# 40_Temp.net
KiCad netlist of a schematic drawn in Altium Designer
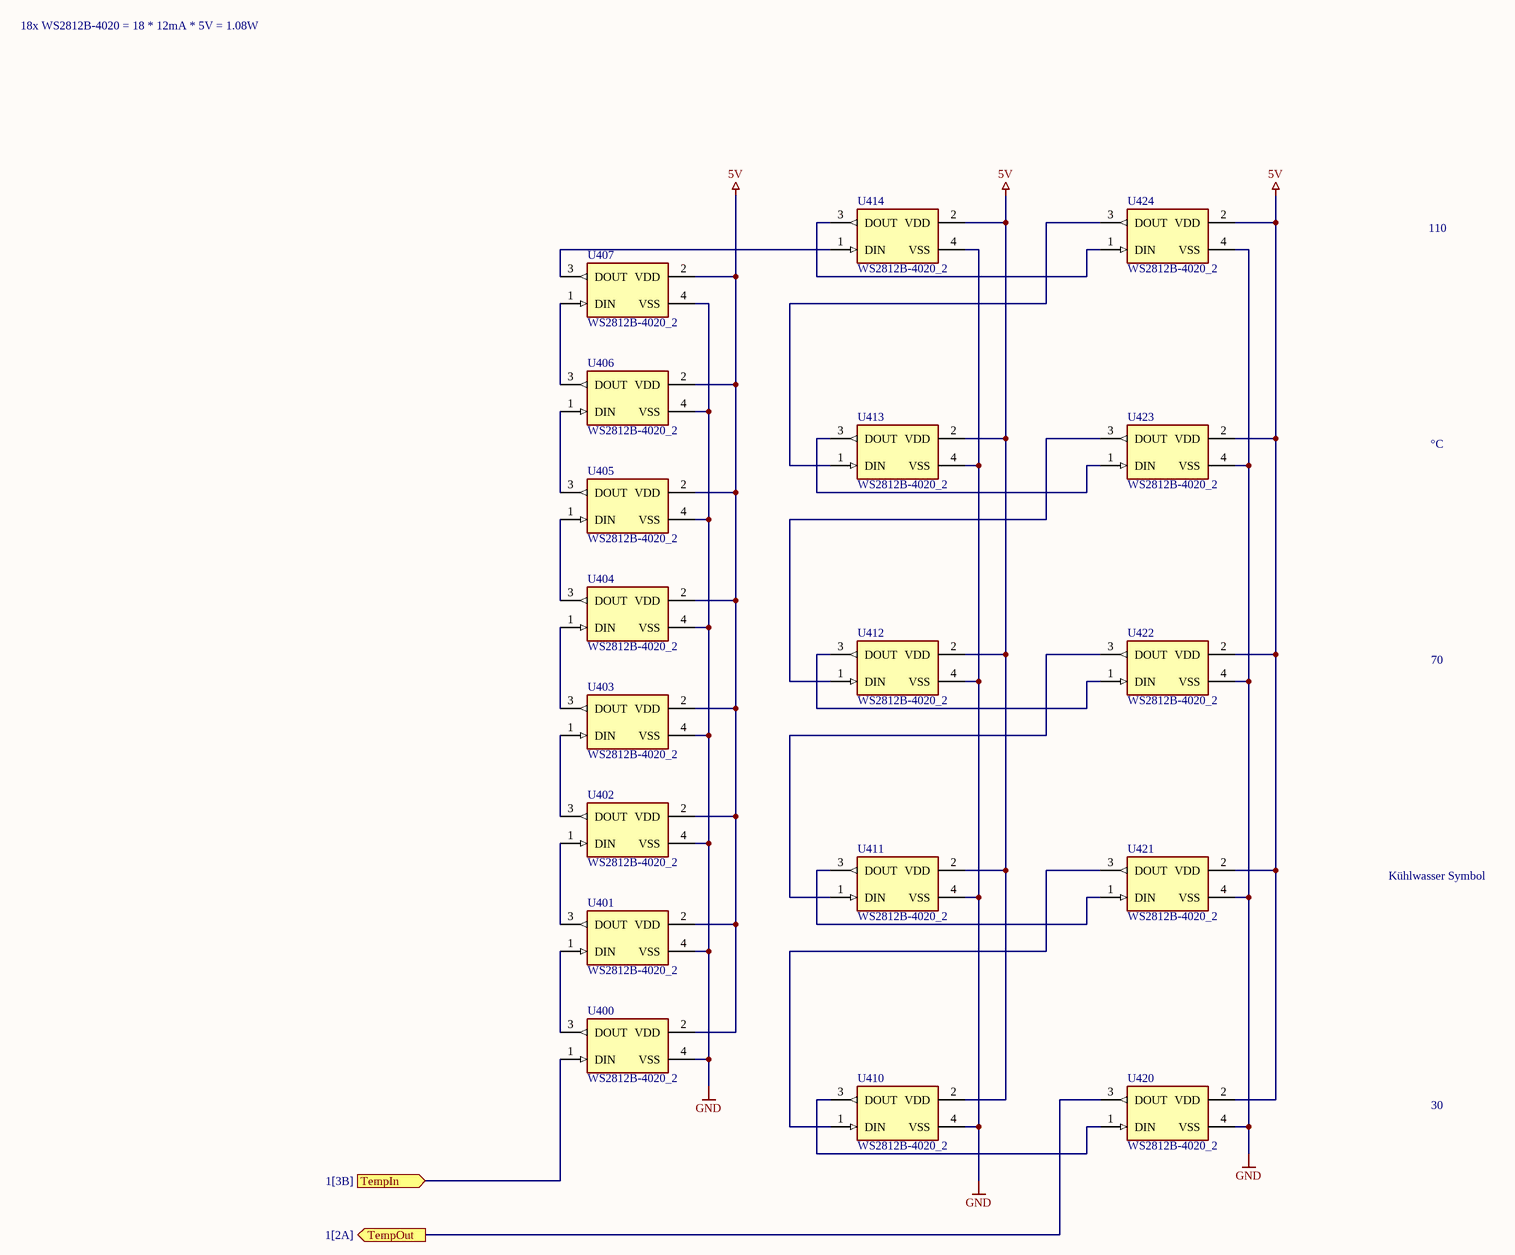
[diagram p0: 40_Temp.SchDoc]

(export (version "E")
  (design (tool "Eeschema 10.0.6"))
  (components
    (comp (ref "U400")
      (value "WS2812B-4020_2")
      (footprint "LED_WS2812B-4020")
      (description "12mA RGB SMD,2x4mm Light Emitting Diodes")
      (fields (field (name "MP") "WS2812B-4020") (field (name "MF") "Worldsemi"))
      (libsource (lib "AltiumLib_MILUTIN") (part "WS2812B-4020_2"))
    )
    (comp (ref "U401")
      (value "WS2812B-4020_2")
      (footprint "LED_WS2812B-4020")
      (description "12mA RGB SMD,2x4mm Light Emitting Diodes")
      (fields (field (name "MP") "WS2812B-4020") (field (name "MF") "Worldsemi"))
      (libsource (lib "AltiumLib_MILUTIN") (part "WS2812B-4020_2"))
    )
    (comp (ref "U402")
      (value "WS2812B-4020_2")
      (footprint "LED_WS2812B-4020")
      (description "12mA RGB SMD,2x4mm Light Emitting Diodes")
      (fields (field (name "MP") "WS2812B-4020") (field (name "MF") "Worldsemi"))
      (libsource (lib "AltiumLib_MILUTIN") (part "WS2812B-4020_2"))
    )
    (comp (ref "U403")
      (value "WS2812B-4020_2")
      (footprint "LED_WS2812B-4020")
      (description "12mA RGB SMD,2x4mm Light Emitting Diodes")
      (fields (field (name "MP") "WS2812B-4020") (field (name "MF") "Worldsemi"))
      (libsource (lib "AltiumLib_MILUTIN") (part "WS2812B-4020_2"))
    )
    (comp (ref "U404")
      (value "WS2812B-4020_2")
      (footprint "LED_WS2812B-4020")
      (description "12mA RGB SMD,2x4mm Light Emitting Diodes")
      (fields (field (name "MP") "WS2812B-4020") (field (name "MF") "Worldsemi"))
      (libsource (lib "AltiumLib_MILUTIN") (part "WS2812B-4020_2"))
    )
    (comp (ref "U405")
      (value "WS2812B-4020_2")
      (footprint "LED_WS2812B-4020")
      (description "12mA RGB SMD,2x4mm Light Emitting Diodes")
      (fields (field (name "MP") "WS2812B-4020") (field (name "MF") "Worldsemi"))
      (libsource (lib "AltiumLib_MILUTIN") (part "WS2812B-4020_2"))
    )
    (comp (ref "U406")
      (value "WS2812B-4020_2")
      (footprint "LED_WS2812B-4020")
      (description "12mA RGB SMD,2x4mm Light Emitting Diodes")
      (fields (field (name "MP") "WS2812B-4020") (field (name "MF") "Worldsemi"))
      (libsource (lib "AltiumLib_MILUTIN") (part "WS2812B-4020_2"))
    )
    (comp (ref "U407")
      (value "WS2812B-4020_2")
      (footprint "LED_WS2812B-4020")
      (description "12mA RGB SMD,2x4mm Light Emitting Diodes")
      (fields (field (name "MP") "WS2812B-4020") (field (name "MF") "Worldsemi"))
      (libsource (lib "AltiumLib_MILUTIN") (part "WS2812B-4020_2"))
    )
    (comp (ref "U410")
      (value "WS2812B-4020_2")
      (footprint "LED_WS2812B-4020")
      (description "12mA RGB SMD,2x4mm Light Emitting Diodes")
      (fields (field (name "MP") "WS2812B-4020") (field (name "MF") "Worldsemi"))
      (libsource (lib "AltiumLib_MILUTIN") (part "WS2812B-4020_2"))
    )
    (comp (ref "U411")
      (value "WS2812B-4020_2")
      (footprint "LED_WS2812B-4020")
      (description "12mA RGB SMD,2x4mm Light Emitting Diodes")
      (fields (field (name "MP") "WS2812B-4020") (field (name "MF") "Worldsemi"))
      (libsource (lib "AltiumLib_MILUTIN") (part "WS2812B-4020_2"))
    )
    (comp (ref "U412")
      (value "WS2812B-4020_2")
      (footprint "LED_WS2812B-4020")
      (description "12mA RGB SMD,2x4mm Light Emitting Diodes")
      (fields (field (name "MP") "WS2812B-4020") (field (name "MF") "Worldsemi"))
      (libsource (lib "AltiumLib_MILUTIN") (part "WS2812B-4020_2"))
    )
    (comp (ref "U413")
      (value "WS2812B-4020_2")
      (footprint "LED_WS2812B-4020")
      (description "12mA RGB SMD,2x4mm Light Emitting Diodes")
      (fields (field (name "MP") "WS2812B-4020") (field (name "MF") "Worldsemi"))
      (libsource (lib "AltiumLib_MILUTIN") (part "WS2812B-4020_2"))
    )
    (comp (ref "U414")
      (value "WS2812B-4020_2")
      (footprint "LED_WS2812B-4020")
      (description "12mA RGB SMD,2x4mm Light Emitting Diodes")
      (fields (field (name "MP") "WS2812B-4020") (field (name "MF") "Worldsemi"))
      (libsource (lib "AltiumLib_MILUTIN") (part "WS2812B-4020_2"))
    )
    (comp (ref "U420")
      (value "WS2812B-4020_2")
      (footprint "LED_WS2812B-4020")
      (description "12mA RGB SMD,2x4mm Light Emitting Diodes")
      (fields (field (name "MP") "WS2812B-4020") (field (name "MF") "Worldsemi"))
      (libsource (lib "AltiumLib_MILUTIN") (part "WS2812B-4020_2"))
    )
    (comp (ref "U421")
      (value "WS2812B-4020_2")
      (footprint "LED_WS2812B-4020")
      (description "12mA RGB SMD,2x4mm Light Emitting Diodes")
      (fields (field (name "MP") "WS2812B-4020") (field (name "MF") "Worldsemi"))
      (libsource (lib "AltiumLib_MILUTIN") (part "WS2812B-4020_2"))
    )
    (comp (ref "U422")
      (value "WS2812B-4020_2")
      (footprint "LED_WS2812B-4020")
      (description "12mA RGB SMD,2x4mm Light Emitting Diodes")
      (fields (field (name "MP") "WS2812B-4020") (field (name "MF") "Worldsemi"))
      (libsource (lib "AltiumLib_MILUTIN") (part "WS2812B-4020_2"))
    )
    (comp (ref "U423")
      (value "WS2812B-4020_2")
      (footprint "LED_WS2812B-4020")
      (description "12mA RGB SMD,2x4mm Light Emitting Diodes")
      (fields (field (name "MP") "WS2812B-4020") (field (name "MF") "Worldsemi"))
      (libsource (lib "AltiumLib_MILUTIN") (part "WS2812B-4020_2"))
    )
    (comp (ref "U424")
      (value "WS2812B-4020_2")
      (footprint "LED_WS2812B-4020")
      (description "12mA RGB SMD,2x4mm Light Emitting Diodes")
      (fields (field (name "MP") "WS2812B-4020") (field (name "MF") "Worldsemi"))
      (libsource (lib "AltiumLib_MILUTIN") (part "WS2812B-4020_2"))
    )
  )
  (nets
    (net (code "1") (name "/TempIn") (class "Default")
      (node (ref "U400") (pin "1") (pinfunction "DIN_1") (pintype "input"))
    )
    (net (code "2") (name "/TempOut") (class "Default")
      (node (ref "U420") (pin "3") (pinfunction "DOUT_3") (pintype "output"))
    )
    (net (code "3") (name "5V") (class "Default")
      (node (ref "U400") (pin "2") (pinfunction "VDD_2") (pintype "power_in"))
      (node (ref "U401") (pin "2") (pinfunction "VDD_2") (pintype "power_in"))
      (node (ref "U402") (pin "2") (pinfunction "VDD_2") (pintype "power_in"))
      (node (ref "U403") (pin "2") (pinfunction "VDD_2") (pintype "power_in"))
      (node (ref "U404") (pin "2") (pinfunction "VDD_2") (pintype "power_in"))
      (node (ref "U405") (pin "2") (pinfunction "VDD_2") (pintype "power_in"))
      (node (ref "U406") (pin "2") (pinfunction "VDD_2") (pintype "power_in"))
      (node (ref "U407") (pin "2") (pinfunction "VDD_2") (pintype "power_in"))
      (node (ref "U410") (pin "2") (pinfunction "VDD_2") (pintype "power_in"))
      (node (ref "U411") (pin "2") (pinfunction "VDD_2") (pintype "power_in"))
      (node (ref "U412") (pin "2") (pinfunction "VDD_2") (pintype "power_in"))
      (node (ref "U413") (pin "2") (pinfunction "VDD_2") (pintype "power_in"))
      (node (ref "U414") (pin "2") (pinfunction "VDD_2") (pintype "power_in"))
      (node (ref "U420") (pin "2") (pinfunction "VDD_2") (pintype "power_in"))
      (node (ref "U421") (pin "2") (pinfunction "VDD_2") (pintype "power_in"))
      (node (ref "U422") (pin "2") (pinfunction "VDD_2") (pintype "power_in"))
      (node (ref "U423") (pin "2") (pinfunction "VDD_2") (pintype "power_in"))
      (node (ref "U424") (pin "2") (pinfunction "VDD_2") (pintype "power_in"))
    )
    (net (code "4") (name "GND") (class "Default")
      (node (ref "U400") (pin "4") (pinfunction "VSS_4") (pintype "power_in"))
      (node (ref "U401") (pin "4") (pinfunction "VSS_4") (pintype "power_in"))
      (node (ref "U402") (pin "4") (pinfunction "VSS_4") (pintype "power_in"))
      (node (ref "U403") (pin "4") (pinfunction "VSS_4") (pintype "power_in"))
      (node (ref "U404") (pin "4") (pinfunction "VSS_4") (pintype "power_in"))
      (node (ref "U405") (pin "4") (pinfunction "VSS_4") (pintype "power_in"))
      (node (ref "U406") (pin "4") (pinfunction "VSS_4") (pintype "power_in"))
      (node (ref "U407") (pin "4") (pinfunction "VSS_4") (pintype "power_in"))
      (node (ref "U410") (pin "4") (pinfunction "VSS_4") (pintype "power_in"))
      (node (ref "U411") (pin "4") (pinfunction "VSS_4") (pintype "power_in"))
      (node (ref "U412") (pin "4") (pinfunction "VSS_4") (pintype "power_in"))
      (node (ref "U413") (pin "4") (pinfunction "VSS_4") (pintype "power_in"))
      (node (ref "U414") (pin "4") (pinfunction "VSS_4") (pintype "power_in"))
      (node (ref "U420") (pin "4") (pinfunction "VSS_4") (pintype "power_in"))
      (node (ref "U421") (pin "4") (pinfunction "VSS_4") (pintype "power_in"))
      (node (ref "U422") (pin "4") (pinfunction "VSS_4") (pintype "power_in"))
      (node (ref "U423") (pin "4") (pinfunction "VSS_4") (pintype "power_in"))
      (node (ref "U424") (pin "4") (pinfunction "VSS_4") (pintype "power_in"))
    )
    (net (code "5") (name "Net-(U400-DOUT)") (class "Default")
      (node (ref "U400") (pin "3") (pinfunction "DOUT_3") (pintype "output"))
      (node (ref "U401") (pin "1") (pinfunction "DIN_1") (pintype "input"))
    )
    (net (code "6") (name "Net-(U401-DOUT)") (class "Default")
      (node (ref "U401") (pin "3") (pinfunction "DOUT_3") (pintype "output"))
      (node (ref "U402") (pin "1") (pinfunction "DIN_1") (pintype "input"))
    )
    (net (code "7") (name "Net-(U402-DOUT)") (class "Default")
      (node (ref "U402") (pin "3") (pinfunction "DOUT_3") (pintype "output"))
      (node (ref "U403") (pin "1") (pinfunction "DIN_1") (pintype "input"))
    )
    (net (code "8") (name "Net-(U403-DOUT)") (class "Default")
      (node (ref "U403") (pin "3") (pinfunction "DOUT_3") (pintype "output"))
      (node (ref "U404") (pin "1") (pinfunction "DIN_1") (pintype "input"))
    )
    (net (code "9") (name "Net-(U404-DOUT)") (class "Default")
      (node (ref "U404") (pin "3") (pinfunction "DOUT_3") (pintype "output"))
      (node (ref "U405") (pin "1") (pinfunction "DIN_1") (pintype "input"))
    )
    (net (code "10") (name "Net-(U405-DOUT)") (class "Default")
      (node (ref "U405") (pin "3") (pinfunction "DOUT_3") (pintype "output"))
      (node (ref "U406") (pin "1") (pinfunction "DIN_1") (pintype "input"))
    )
    (net (code "11") (name "Net-(U406-DOUT)") (class "Default")
      (node (ref "U406") (pin "3") (pinfunction "DOUT_3") (pintype "output"))
      (node (ref "U407") (pin "1") (pinfunction "DIN_1") (pintype "input"))
    )
    (net (code "12") (name "Net-(U407-DOUT)") (class "Default")
      (node (ref "U407") (pin "3") (pinfunction "DOUT_3") (pintype "output"))
      (node (ref "U414") (pin "1") (pinfunction "DIN_1") (pintype "input"))
    )
    (net (code "13") (name "Net-(U410-DIN)") (class "Default")
      (node (ref "U410") (pin "1") (pinfunction "DIN_1") (pintype "input"))
      (node (ref "U421") (pin "3") (pinfunction "DOUT_3") (pintype "output"))
    )
    (net (code "14") (name "Net-(U410-DOUT)") (class "Default")
      (node (ref "U410") (pin "3") (pinfunction "DOUT_3") (pintype "output"))
      (node (ref "U420") (pin "1") (pinfunction "DIN_1") (pintype "input"))
    )
    (net (code "15") (name "Net-(U411-DIN)") (class "Default")
      (node (ref "U411") (pin "1") (pinfunction "DIN_1") (pintype "input"))
      (node (ref "U422") (pin "3") (pinfunction "DOUT_3") (pintype "output"))
    )
    (net (code "16") (name "Net-(U411-DOUT)") (class "Default")
      (node (ref "U411") (pin "3") (pinfunction "DOUT_3") (pintype "output"))
      (node (ref "U421") (pin "1") (pinfunction "DIN_1") (pintype "input"))
    )
    (net (code "17") (name "Net-(U412-DIN)") (class "Default")
      (node (ref "U412") (pin "1") (pinfunction "DIN_1") (pintype "input"))
      (node (ref "U423") (pin "3") (pinfunction "DOUT_3") (pintype "output"))
    )
    (net (code "18") (name "Net-(U412-DOUT)") (class "Default")
      (node (ref "U412") (pin "3") (pinfunction "DOUT_3") (pintype "output"))
      (node (ref "U422") (pin "1") (pinfunction "DIN_1") (pintype "input"))
    )
    (net (code "19") (name "Net-(U413-DIN)") (class "Default")
      (node (ref "U413") (pin "1") (pinfunction "DIN_1") (pintype "input"))
      (node (ref "U424") (pin "3") (pinfunction "DOUT_3") (pintype "output"))
    )
    (net (code "20") (name "Net-(U413-DOUT)") (class "Default")
      (node (ref "U413") (pin "3") (pinfunction "DOUT_3") (pintype "output"))
      (node (ref "U423") (pin "1") (pinfunction "DIN_1") (pintype "input"))
    )
    (net (code "21") (name "Net-(U414-DOUT)") (class "Default")
      (node (ref "U414") (pin "3") (pinfunction "DOUT_3") (pintype "output"))
      (node (ref "U424") (pin "1") (pinfunction "DIN_1") (pintype "input"))
    )
  )
)
